# 04-IO.net
KiCad netlist of a schematic drawn in Altium Designer
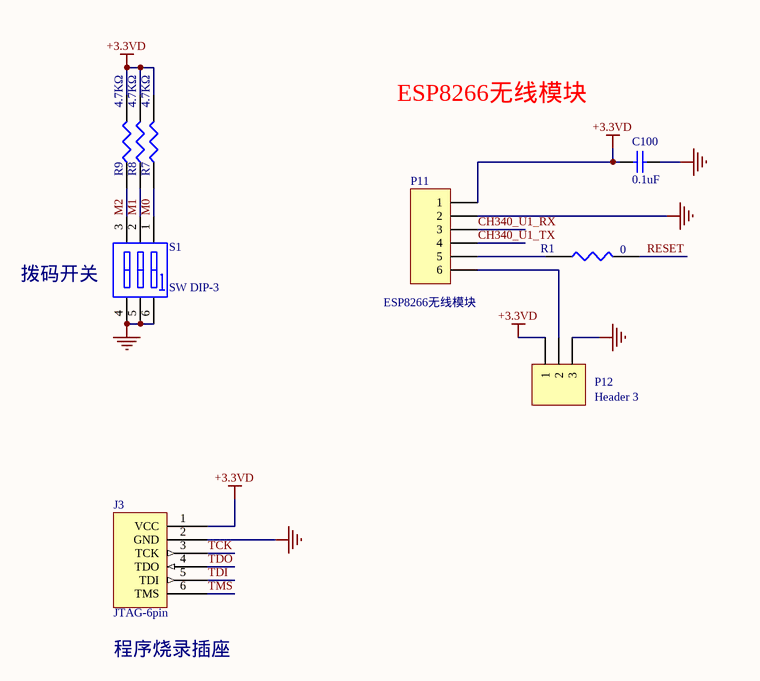
[diagram p0: 04-IO.SchDoc]

(export (version "E")
  (design (tool "Eeschema 10.0.6"))
  (components
    (comp (ref "C100")
      (value "0.1uF")
      (footprint "0402")
      (description "Capacitor")
      (fields (field (name "PUBLISHER") "Altium Limited"))
      (libsource (lib "Miscellaneous Devices") (part "Cap"))
    )
    (comp (ref "J3")
      (value "JTAG-6pin")
      (footprint "SIP6")
      (description "JTAG INTERFACE")
      (libsource (lib "*") (part "JTAG"))
    )
    (comp (ref "P11")
      (value "ESP8266无线模块")
      (footprint "ATK-ESP8266")
      (description "Header, 6-Pin")
      (fields (field (name "PUBLISHER") "Altium Limited"))
      (libsource (lib "Miscellaneous Connectors") (part "Header 6"))
    )
    (comp (ref "P12")
      (value "Header 3")
      (footprint "HDR1X3")
      (description "Header, 3-Pin")
      (fields (field (name "PUBLISHER") "Altium Limited"))
      (libsource (lib "Miscellaneous Connectors") (part "Header 3"))
    )
    (comp (ref "R1") (value "0") (footprint "0805") (libsource (lib "*") (part "RES1")))
    (comp (ref "R7") (value "4.7KΩ") (footprint "0805") (libsource (lib "*") (part "RES1")))
    (comp (ref "R8") (value "4.7KΩ") (footprint "0805") (libsource (lib "*") (part "RES1")))
    (comp (ref "R9") (value "4.7KΩ") (footprint "0805") (libsource (lib "*") (part "RES1")))
    (comp (ref "S1")
      (value "SW DIP-3")
      (footprint "SW3 SMD")
      (description "DIP Switch")
      (libsource (lib "*") (part "SW DIP-3"))
    )
  )
  (nets
    (net (code "1") (name "+3.3VD") (class "Default")
      (node (ref "C100") (pin "1") (pinfunction "1_1") (pintype "passive"))
      (node (ref "J3") (pin "1") (pinfunction "VCC_1") (pintype "power_in"))
      (node (ref "P11") (pin "1") (pinfunction "1_1") (pintype "passive"))
      (node (ref "P12") (pin "1") (pinfunction "1_1") (pintype "passive"))
      (node (ref "R7") (pin "2") (pinfunction "2_2") (pintype "passive"))
      (node (ref "R8") (pin "2") (pinfunction "2_2") (pintype "passive"))
      (node (ref "R9") (pin "2") (pinfunction "2_2") (pintype "passive"))
    )
    (net (code "2") (name "/CH340_U1_RX") (class "Default")
      (node (ref "P11") (pin "3") (pinfunction "3_3") (pintype "passive"))
    )
    (net (code "3") (name "/CH340_U1_TX") (class "Default")
      (node (ref "P11") (pin "4") (pinfunction "4_4") (pintype "passive"))
    )
    (net (code "4") (name "/M0") (class "Default")
      (node (ref "R7") (pin "1") (pinfunction "1_1") (pintype "passive"))
      (node (ref "S1") (pin "1") (pinfunction "A1_1") (pintype "passive"))
    )
    (net (code "5") (name "/M1") (class "Default")
      (node (ref "R8") (pin "1") (pinfunction "1_1") (pintype "passive"))
      (node (ref "S1") (pin "2") (pinfunction "A2_2") (pintype "passive"))
    )
    (net (code "6") (name "/M2") (class "Default")
      (node (ref "R9") (pin "1") (pinfunction "1_1") (pintype "passive"))
      (node (ref "S1") (pin "3") (pinfunction "A3_3") (pintype "passive"))
    )
    (net (code "7") (name "/RESET") (class "Default")
      (node (ref "R1") (pin "2") (pinfunction "2_2") (pintype "passive"))
    )
    (net (code "8") (name "/TCK") (class "Default")
      (node (ref "J3") (pin "3") (pinfunction "TCK_3") (pintype "output"))
    )
    (net (code "9") (name "/TDI") (class "Default")
      (node (ref "J3") (pin "5") (pinfunction "TDI_5") (pintype "output"))
    )
    (net (code "10") (name "/TDO") (class "Default")
      (node (ref "J3") (pin "4") (pinfunction "TDO_4") (pintype "input"))
    )
    (net (code "11") (name "/TMS") (class "Default")
      (node (ref "J3") (pin "6") (pinfunction "TMS_6") (pintype "power_in"))
    )
    (net (code "12") (name "DGND") (class "Default")
      (node (ref "C100") (pin "2") (pinfunction "2_2") (pintype "passive"))
      (node (ref "J3") (pin "2") (pinfunction "GND_2") (pintype "power_in"))
      (node (ref "P11") (pin "2") (pinfunction "2_2") (pintype "passive"))
      (node (ref "P12") (pin "3") (pinfunction "3_3") (pintype "passive"))
      (node (ref "S1") (pin "4") (pinfunction "B3_4") (pintype "passive"))
      (node (ref "S1") (pin "5") (pinfunction "B2_5") (pintype "passive"))
      (node (ref "S1") (pin "6") (pinfunction "B1_6") (pintype "passive"))
    )
    (net (code "13") (name "Net-(P11-Pad5)") (class "Default")
      (node (ref "P11") (pin "5") (pinfunction "5_5") (pintype "passive"))
      (node (ref "R1") (pin "1") (pinfunction "1_1") (pintype "passive"))
    )
    (net (code "14") (name "Net-(P11-Pad6)") (class "Default")
      (node (ref "P11") (pin "6") (pinfunction "6_6") (pintype "passive"))
      (node (ref "P12") (pin "2") (pinfunction "2_2") (pintype "passive"))
    )
  )
)
